# Flash.net
KiCad netlist of a schematic drawn in Altium Designer
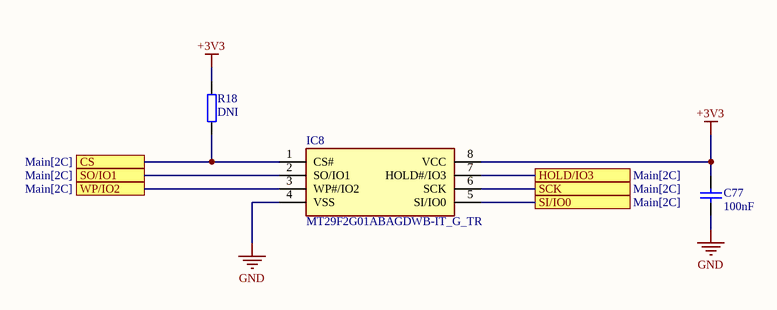
[diagram p0: Flash.SchDoc]

(export (version "E")
  (design (tool "Eeschema 10.0.6"))
  (components
    (comp (ref "C77")
      (value "100nF")
      (footprint "CAP0402")
      (fields
        (field (name "VOLTAGE") "50V")
        (field (name "MANUFACTURER_PART_NUMBER") "GRM155R71H104ME14D")
        (field (name "Comment") "Cap0402")
      )
      (libsource (lib "capacitorsSMD") (part "Cap0402"))
    )
    (comp (ref "IC8")
      (value "MT29F2G01ABAGDWB-IT_G_TR")
      (footprint "SamacSys:SON127P800X600X65-8N")
      (description "Integrated Circuit")
      (fields
        (field (name "MANUFACTURER_PART_NUMBER") "MT29F2G01ABAGDWB-IT:G TR")
        (field (name "MOUSER PART NUMBER") "340-319922-REEL")
      )
      (libsource (lib "*") (part "MT29F2G01ABAGDWB-IT_G_TR"))
    )
    (comp (ref "R18")
      (value "DNI")
      (footprint "RES0402")
      (fields (field (name "Comment") "Res0402"))
      (libsource (lib "resistorSMD") (part "Res0402"))
    )
  )
  (nets
    (net (code "1") (name "+3V3") (class "Default")
      (node (ref "C77") (pin "2") (pinfunction "2_2") (pintype "passive"))
      (node (ref "IC8") (pin "8") (pinfunction "VCC_8") (pintype "passive"))
      (node (ref "R18") (pin "2") (pinfunction "2_2") (pintype "passive"))
    )
    (net (code "2") (name "/CS") (class "Default")
      (node (ref "IC8") (pin "1") (pinfunction "CS#_1") (pintype "passive"))
      (node (ref "R18") (pin "1") (pinfunction "1_1") (pintype "passive"))
    )
    (net (code "3") (name "/HOLD{slash}IO3") (class "Default")
      (node (ref "IC8") (pin "7") (pinfunction "HOLD#/IO3_7") (pintype "passive"))
    )
    (net (code "4") (name "/SCK") (class "Default")
      (node (ref "IC8") (pin "6") (pinfunction "SCK_6") (pintype "passive"))
    )
    (net (code "5") (name "/SI{slash}IO0") (class "Default")
      (node (ref "IC8") (pin "5") (pinfunction "SI/IO0_5") (pintype "passive"))
    )
    (net (code "6") (name "/SO{slash}IO1") (class "Default")
      (node (ref "IC8") (pin "2") (pinfunction "SO/IO1_2") (pintype "passive"))
    )
    (net (code "7") (name "/WP{slash}IO2") (class "Default")
      (node (ref "IC8") (pin "3") (pinfunction "WP#/IO2_3") (pintype "passive"))
    )
    (net (code "8") (name "GND") (class "Default")
      (node (ref "C77") (pin "1") (pinfunction "1_1") (pintype "passive"))
      (node (ref "IC8") (pin "4") (pinfunction "VSS_4") (pintype "passive"))
    )
  )
)
